# connector_board.net
KiCad netlist of a schematic drawn in EAGLE
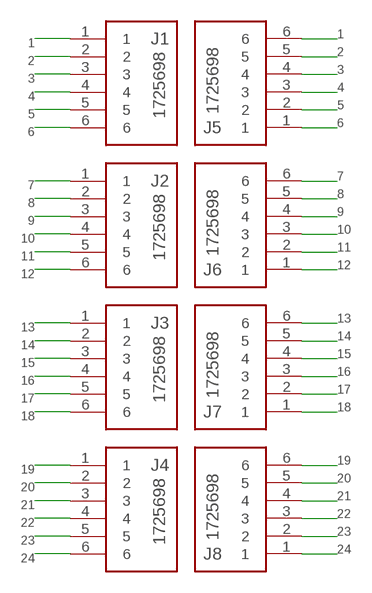
[diagram p0: schematic, sheet 1]

(export (version "E")
  (design (tool "Eeschema 10.0.6"))
  (components
    (comp (ref "J1")
      (value "1725698")
      (footprint "eagle-import:SHDR6W90P0X254_1X6_1570X620X85")
      (fields (field (name "RS_PART_NUMBER") "3909045"))
      (libsource (lib "eagle-import") (part "1725698"))
    )
    (comp (ref "J2")
      (value "1725698")
      (footprint "eagle-import:SHDR6W90P0X254_1X6_1570X620X85")
      (fields (field (name "RS_PART_NUMBER") "3909045"))
      (libsource (lib "eagle-import") (part "1725698"))
    )
    (comp (ref "J3")
      (value "1725698")
      (footprint "eagle-import:SHDR6W90P0X254_1X6_1570X620X85")
      (fields (field (name "RS_PART_NUMBER") "3909045"))
      (libsource (lib "eagle-import") (part "1725698"))
    )
    (comp (ref "J4")
      (value "1725698")
      (footprint "eagle-import:SHDR6W90P0X254_1X6_1570X620X85")
      (fields (field (name "RS_PART_NUMBER") "3909045"))
      (libsource (lib "eagle-import") (part "1725698"))
    )
    (comp (ref "J5")
      (value "1725698")
      (footprint "eagle-import:SHDR6W90P0X254_1X6_1570X620X85")
      (fields (field (name "RS_PART_NUMBER") "3909045"))
      (libsource (lib "eagle-import") (part "1725698"))
    )
    (comp (ref "J6")
      (value "1725698")
      (footprint "eagle-import:SHDR6W90P0X254_1X6_1570X620X85")
      (fields (field (name "RS_PART_NUMBER") "3909045"))
      (libsource (lib "eagle-import") (part "1725698"))
    )
    (comp (ref "J7")
      (value "1725698")
      (footprint "eagle-import:SHDR6W90P0X254_1X6_1570X620X85")
      (fields (field (name "RS_PART_NUMBER") "3909045"))
      (libsource (lib "eagle-import") (part "1725698"))
    )
    (comp (ref "J8")
      (value "1725698")
      (footprint "eagle-import:SHDR6W90P0X254_1X6_1570X620X85")
      (fields (field (name "RS_PART_NUMBER") "3909045"))
      (libsource (lib "eagle-import") (part "1725698"))
    )
  )
  (nets
    (net (code "1") (name "1") (class "Default")
      (node (ref "J1") (pin "1") (pinfunction "1_1") (pintype "bidirectional"))
      (node (ref "J5") (pin "6") (pinfunction "6_6") (pintype "bidirectional"))
    )
    (net (code "2") (name "2") (class "Default")
      (node (ref "J1") (pin "2") (pinfunction "2_2") (pintype "bidirectional"))
      (node (ref "J5") (pin "5") (pinfunction "5_5") (pintype "bidirectional"))
    )
    (net (code "3") (name "3") (class "Default")
      (node (ref "J1") (pin "3") (pinfunction "3_3") (pintype "bidirectional"))
      (node (ref "J5") (pin "4") (pinfunction "4_4") (pintype "bidirectional"))
    )
    (net (code "4") (name "4") (class "Default")
      (node (ref "J1") (pin "4") (pinfunction "4_4") (pintype "bidirectional"))
      (node (ref "J5") (pin "3") (pinfunction "3_3") (pintype "bidirectional"))
    )
    (net (code "5") (name "5") (class "Default")
      (node (ref "J1") (pin "5") (pinfunction "5_5") (pintype "bidirectional"))
      (node (ref "J5") (pin "2") (pinfunction "2_2") (pintype "bidirectional"))
    )
    (net (code "6") (name "6") (class "Default")
      (node (ref "J1") (pin "6") (pinfunction "6_6") (pintype "bidirectional"))
      (node (ref "J5") (pin "1") (pinfunction "1_1") (pintype "bidirectional"))
    )
    (net (code "7") (name "7") (class "Default")
      (node (ref "J2") (pin "1") (pinfunction "1_1") (pintype "bidirectional"))
      (node (ref "J6") (pin "6") (pinfunction "6_6") (pintype "bidirectional"))
    )
    (net (code "8") (name "8") (class "Default")
      (node (ref "J2") (pin "2") (pinfunction "2_2") (pintype "bidirectional"))
      (node (ref "J6") (pin "5") (pinfunction "5_5") (pintype "bidirectional"))
    )
    (net (code "9") (name "9") (class "Default")
      (node (ref "J2") (pin "3") (pinfunction "3_3") (pintype "bidirectional"))
      (node (ref "J6") (pin "4") (pinfunction "4_4") (pintype "bidirectional"))
    )
    (net (code "10") (name "10") (class "Default")
      (node (ref "J2") (pin "4") (pinfunction "4_4") (pintype "bidirectional"))
      (node (ref "J6") (pin "3") (pinfunction "3_3") (pintype "bidirectional"))
    )
    (net (code "11") (name "11") (class "Default")
      (node (ref "J2") (pin "5") (pinfunction "5_5") (pintype "bidirectional"))
      (node (ref "J6") (pin "2") (pinfunction "2_2") (pintype "bidirectional"))
    )
    (net (code "12") (name "12") (class "Default")
      (node (ref "J2") (pin "6") (pinfunction "6_6") (pintype "bidirectional"))
      (node (ref "J6") (pin "1") (pinfunction "1_1") (pintype "bidirectional"))
    )
    (net (code "13") (name "13") (class "Default")
      (node (ref "J3") (pin "1") (pinfunction "1_1") (pintype "bidirectional"))
      (node (ref "J7") (pin "6") (pinfunction "6_6") (pintype "bidirectional"))
    )
    (net (code "14") (name "14") (class "Default")
      (node (ref "J3") (pin "2") (pinfunction "2_2") (pintype "bidirectional"))
      (node (ref "J7") (pin "5") (pinfunction "5_5") (pintype "bidirectional"))
    )
    (net (code "15") (name "15") (class "Default")
      (node (ref "J3") (pin "3") (pinfunction "3_3") (pintype "bidirectional"))
      (node (ref "J7") (pin "4") (pinfunction "4_4") (pintype "bidirectional"))
    )
    (net (code "16") (name "16") (class "Default")
      (node (ref "J3") (pin "4") (pinfunction "4_4") (pintype "bidirectional"))
      (node (ref "J7") (pin "3") (pinfunction "3_3") (pintype "bidirectional"))
    )
    (net (code "17") (name "17") (class "Default")
      (node (ref "J3") (pin "5") (pinfunction "5_5") (pintype "bidirectional"))
      (node (ref "J7") (pin "2") (pinfunction "2_2") (pintype "bidirectional"))
    )
    (net (code "18") (name "18") (class "Default")
      (node (ref "J3") (pin "6") (pinfunction "6_6") (pintype "bidirectional"))
      (node (ref "J7") (pin "1") (pinfunction "1_1") (pintype "bidirectional"))
    )
    (net (code "19") (name "19") (class "Default")
      (node (ref "J4") (pin "1") (pinfunction "1_1") (pintype "bidirectional"))
      (node (ref "J8") (pin "6") (pinfunction "6_6") (pintype "bidirectional"))
    )
    (net (code "20") (name "20") (class "Default")
      (node (ref "J4") (pin "2") (pinfunction "2_2") (pintype "bidirectional"))
      (node (ref "J8") (pin "5") (pinfunction "5_5") (pintype "bidirectional"))
    )
    (net (code "21") (name "21") (class "Default")
      (node (ref "J4") (pin "3") (pinfunction "3_3") (pintype "bidirectional"))
      (node (ref "J8") (pin "4") (pinfunction "4_4") (pintype "bidirectional"))
    )
    (net (code "22") (name "22") (class "Default")
      (node (ref "J4") (pin "4") (pinfunction "4_4") (pintype "bidirectional"))
      (node (ref "J8") (pin "3") (pinfunction "3_3") (pintype "bidirectional"))
    )
    (net (code "23") (name "23") (class "Default")
      (node (ref "J4") (pin "5") (pinfunction "5_5") (pintype "bidirectional"))
      (node (ref "J8") (pin "2") (pinfunction "2_2") (pintype "bidirectional"))
    )
    (net (code "24") (name "24") (class "Default")
      (node (ref "J4") (pin "6") (pinfunction "6_6") (pintype "bidirectional"))
      (node (ref "J8") (pin "1") (pinfunction "1_1") (pintype "bidirectional"))
    )
  )
)
